# esp32_display_schema.net
KiCad netlist of a schematic drawn in EasyEDA
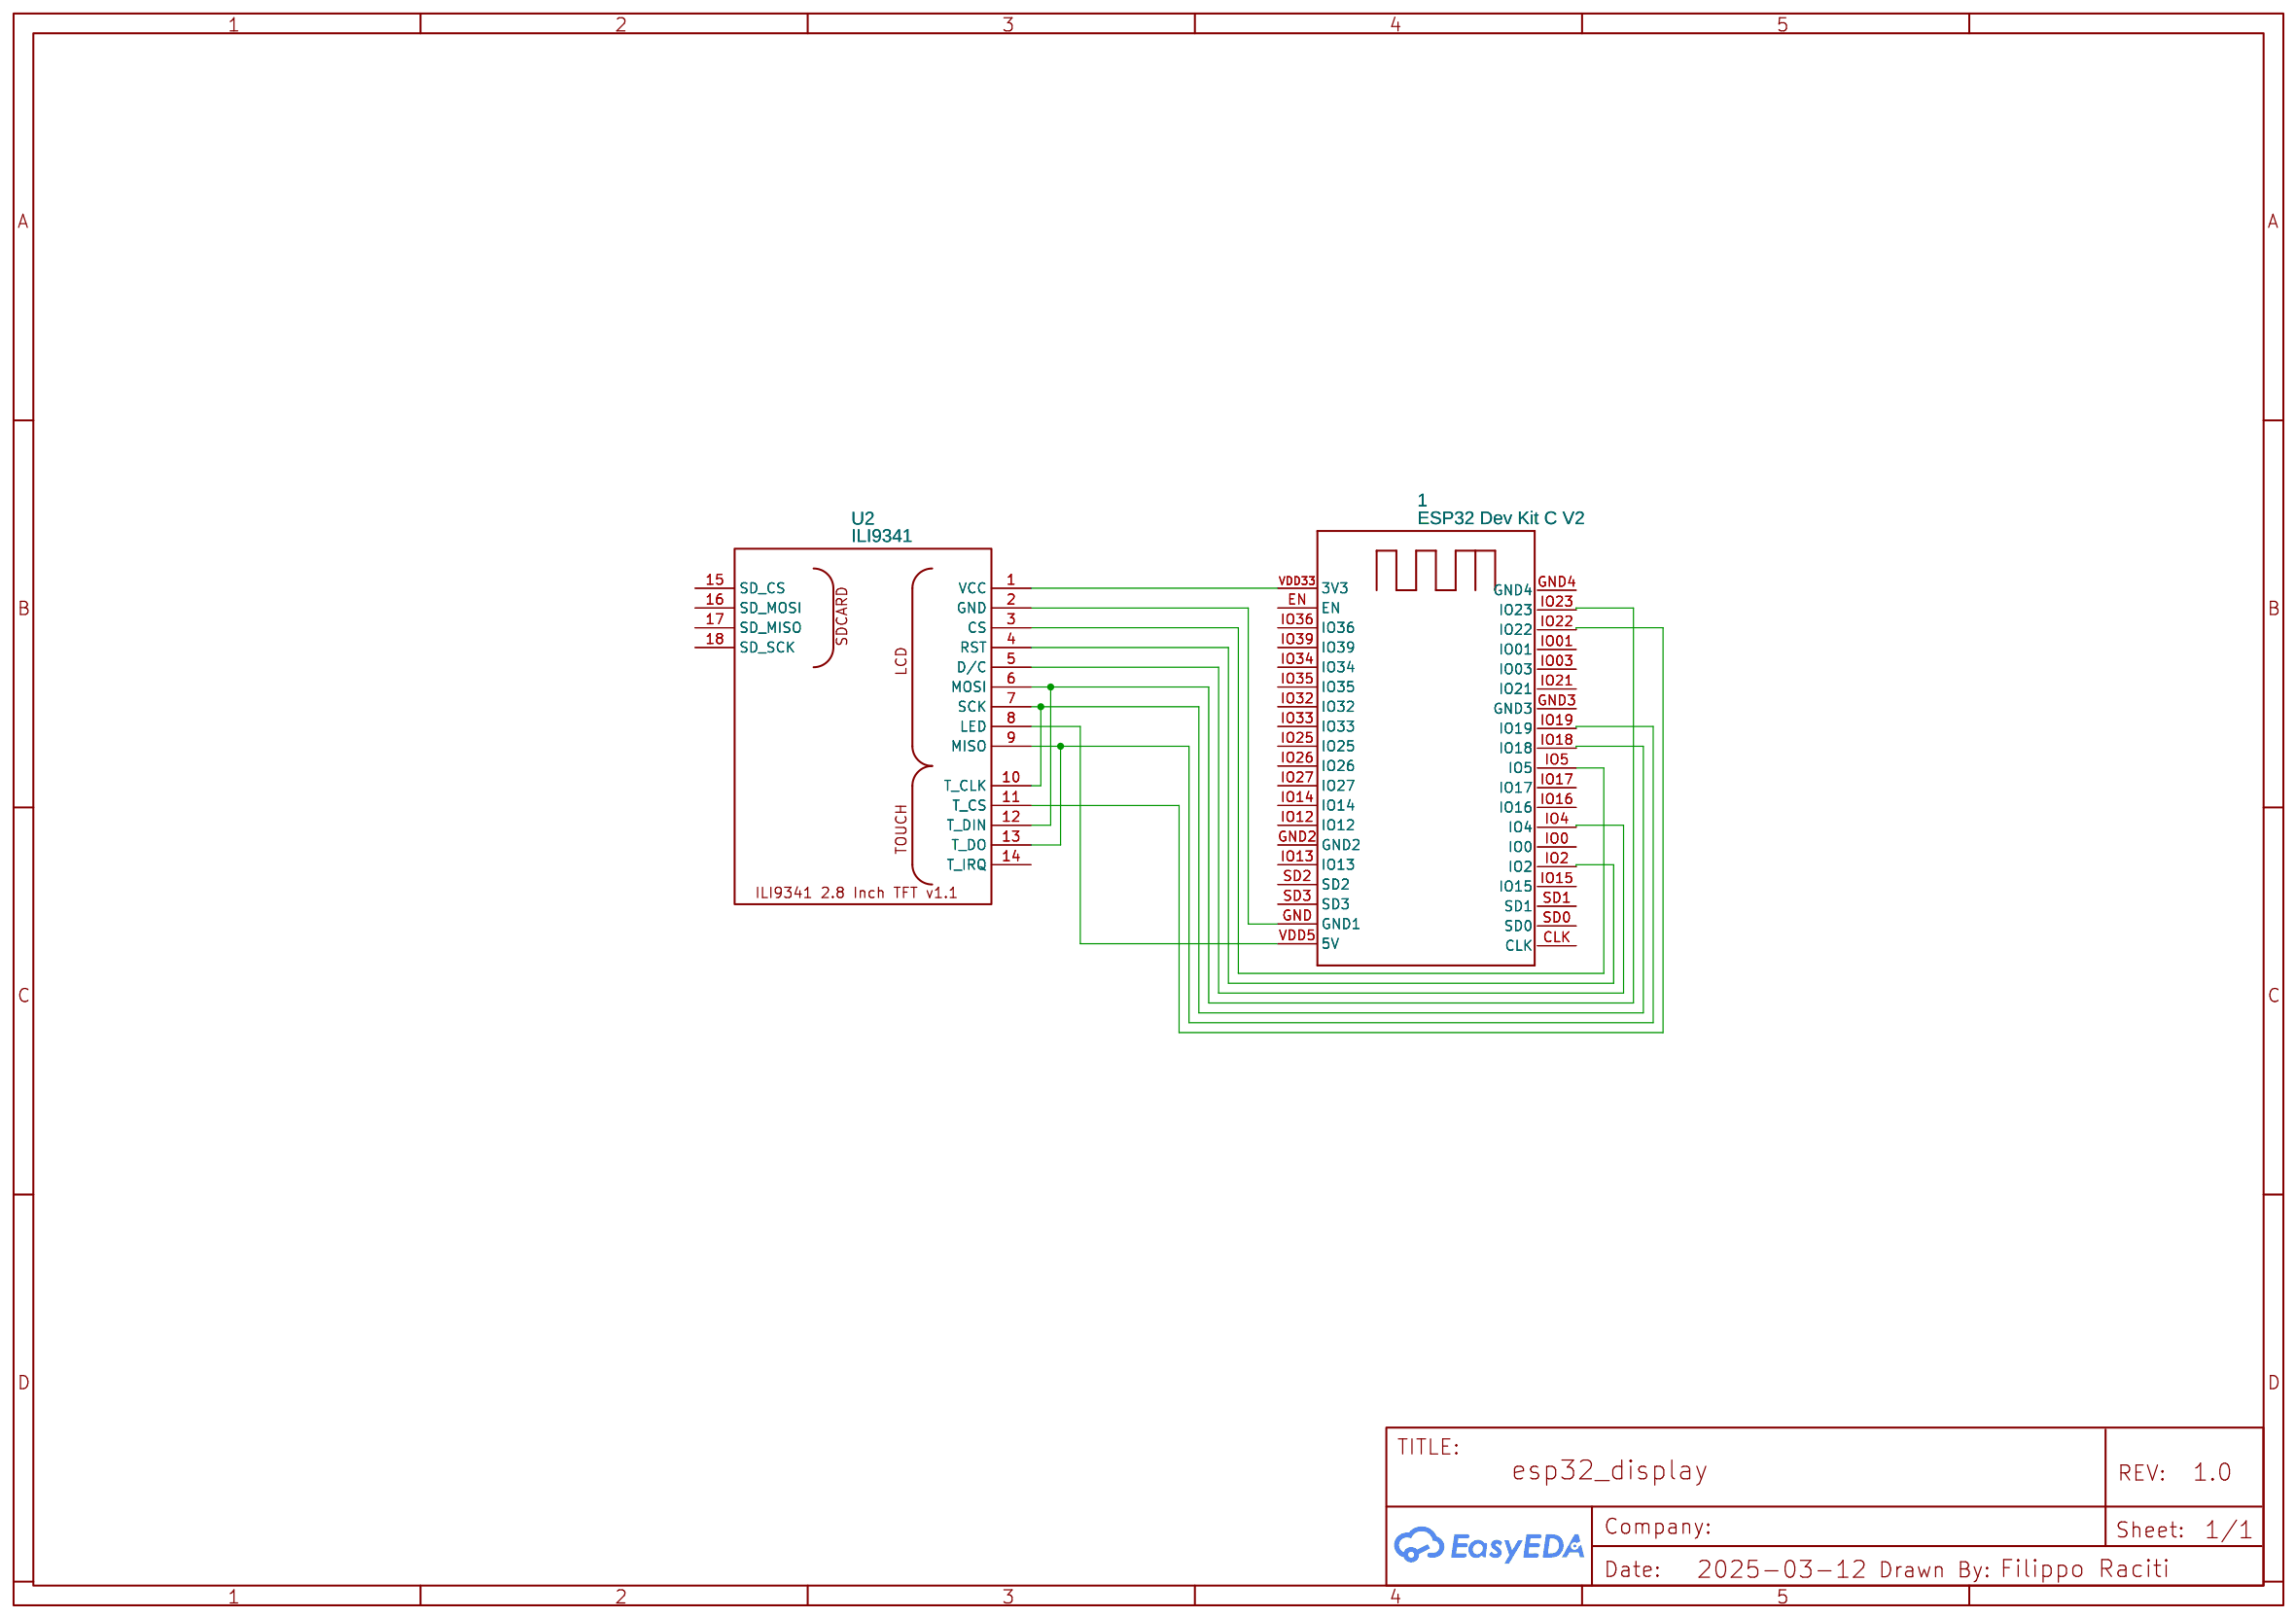
[diagram p0: schematic sheet]

(export (version "E")
  (design (tool "Eeschema 10.0.6"))
  (components
    (comp (ref "1") (value "ESP32 Dev Kit C V2") (libsource (lib "") (part "ESP32 Dev Kit C V2")))
    (comp (ref "U2") (value "ILI9341") (libsource (lib "") (part "ILI9341")))
  )
  (nets
    (net (code "1") (name "Net-(1-3V3)") (class "Default")
      (node (ref "1") (pin "VDD33") (pinfunction "3V3_VDD33") (pintype "unspecified"))
      (node (ref "U2") (pin "1") (pinfunction "VCC_1") (pintype "unspecified"))
    )
    (net (code "2") (name "Net-(1-5V)") (class "Default")
      (node (ref "1") (pin "VDD5") (pinfunction "5V_VDD5") (pintype "unspecified"))
      (node (ref "U2") (pin "8") (pinfunction "LED_8") (pintype "unspecified"))
    )
    (net (code "3") (name "Net-(1-GND1)") (class "Default")
      (node (ref "1") (pin "GND") (pinfunction "GND1_GND") (pintype "unspecified"))
      (node (ref "U2") (pin "2") (pinfunction "GND_2") (pintype "unspecified"))
    )
    (net (code "4") (name "Net-(U2-CS)") (class "Default")
      (node (ref "1") (pin "IO5") (pinfunction "IO5_IO5") (pintype "unspecified"))
      (node (ref "U2") (pin "3") (pinfunction "CS_3") (pintype "unspecified"))
    )
    (net (code "5") (name "Net-(U2-D{slash}C)") (class "Default")
      (node (ref "1") (pin "IO4") (pinfunction "IO4_IO4") (pintype "unspecified"))
      (node (ref "U2") (pin "5") (pinfunction "D/C_5") (pintype "unspecified"))
    )
    (net (code "6") (name "Net-(U2-MISO)") (class "Default")
      (node (ref "1") (pin "IO19") (pinfunction "IO19_IO19") (pintype "unspecified"))
      (node (ref "U2") (pin "13") (pinfunction "T_DO_13") (pintype "unspecified"))
      (node (ref "U2") (pin "9") (pinfunction "MISO_9") (pintype "unspecified"))
    )
    (net (code "7") (name "Net-(U2-MOSI)") (class "Default")
      (node (ref "1") (pin "IO23") (pinfunction "IO23_IO23") (pintype "unspecified"))
      (node (ref "U2") (pin "12") (pinfunction "T_DIN_12") (pintype "unspecified"))
      (node (ref "U2") (pin "6") (pinfunction "MOSI_6") (pintype "unspecified"))
    )
    (net (code "8") (name "Net-(U2-RST)") (class "Default")
      (node (ref "1") (pin "IO2") (pinfunction "IO2_IO2") (pintype "unspecified"))
      (node (ref "U2") (pin "4") (pinfunction "RST_4") (pintype "unspecified"))
    )
    (net (code "9") (name "Net-(U2-SCK)") (class "Default")
      (node (ref "1") (pin "IO18") (pinfunction "IO18_IO18") (pintype "unspecified"))
      (node (ref "U2") (pin "10") (pinfunction "T_CLK_10") (pintype "unspecified"))
      (node (ref "U2") (pin "7") (pinfunction "SCK_7") (pintype "unspecified"))
    )
    (net (code "10") (name "Net-(U2-T_CS)") (class "Default")
      (node (ref "1") (pin "IO22") (pinfunction "IO22_IO22") (pintype "unspecified"))
      (node (ref "U2") (pin "11") (pinfunction "T_CS_11") (pintype "unspecified"))
    )
    (net (code "11") (name "unconnected-(1-PadCLK)") (class "Default")
      (node (ref "1") (pin "CLK") (pinfunction "CLK_CLK") (pintype "unspecified"))
    )
    (net (code "12") (name "unconnected-(1-PadEN)") (class "Default")
      (node (ref "1") (pin "EN") (pinfunction "EN_EN") (pintype "unspecified"))
    )
    (net (code "13") (name "unconnected-(1-PadGND2)") (class "Default")
      (node (ref "1") (pin "GND2") (pinfunction "GND2_GND2") (pintype "unspecified"))
    )
    (net (code "14") (name "unconnected-(1-PadGND3)") (class "Default")
      (node (ref "1") (pin "GND3") (pinfunction "GND3_GND3") (pintype "unspecified"))
    )
    (net (code "15") (name "unconnected-(1-PadGND4)") (class "Default")
      (node (ref "1") (pin "GND4") (pinfunction "GND4_GND4") (pintype "unspecified"))
    )
    (net (code "16") (name "unconnected-(1-PadIO0)") (class "Default")
      (node (ref "1") (pin "IO0") (pinfunction "IO0_IO0") (pintype "unspecified"))
    )
    (net (code "17") (name "unconnected-(1-PadIO01)") (class "Default")
      (node (ref "1") (pin "IO01") (pinfunction "IO01_IO01") (pintype "unspecified"))
    )
    (net (code "18") (name "unconnected-(1-PadIO03)") (class "Default")
      (node (ref "1") (pin "IO03") (pinfunction "IO03_IO03") (pintype "unspecified"))
    )
    (net (code "19") (name "unconnected-(1-PadIO12)") (class "Default")
      (node (ref "1") (pin "IO12") (pinfunction "IO12_IO12") (pintype "unspecified"))
    )
    (net (code "20") (name "unconnected-(1-PadIO13)") (class "Default")
      (node (ref "1") (pin "IO13") (pinfunction "IO13_IO13") (pintype "unspecified"))
    )
    (net (code "21") (name "unconnected-(1-PadIO14)") (class "Default")
      (node (ref "1") (pin "IO14") (pinfunction "IO14_IO14") (pintype "unspecified"))
    )
    (net (code "22") (name "unconnected-(1-PadIO15)") (class "Default")
      (node (ref "1") (pin "IO15") (pinfunction "IO15_IO15") (pintype "unspecified"))
    )
    (net (code "23") (name "unconnected-(1-PadIO16)") (class "Default")
      (node (ref "1") (pin "IO16") (pinfunction "IO16_IO16") (pintype "unspecified"))
    )
    (net (code "24") (name "unconnected-(1-PadIO17)") (class "Default")
      (node (ref "1") (pin "IO17") (pinfunction "IO17_IO17") (pintype "unspecified"))
    )
    (net (code "25") (name "unconnected-(1-PadIO21)") (class "Default")
      (node (ref "1") (pin "IO21") (pinfunction "IO21_IO21") (pintype "unspecified"))
    )
    (net (code "26") (name "unconnected-(1-PadIO25)") (class "Default")
      (node (ref "1") (pin "IO25") (pinfunction "IO25_IO25") (pintype "unspecified"))
    )
    (net (code "27") (name "unconnected-(1-PadIO26)") (class "Default")
      (node (ref "1") (pin "IO26") (pinfunction "IO26_IO26") (pintype "unspecified"))
    )
    (net (code "28") (name "unconnected-(1-PadIO27)") (class "Default")
      (node (ref "1") (pin "IO27") (pinfunction "IO27_IO27") (pintype "unspecified"))
    )
    (net (code "29") (name "unconnected-(1-PadIO32)") (class "Default")
      (node (ref "1") (pin "IO32") (pinfunction "IO32_IO32") (pintype "unspecified"))
    )
    (net (code "30") (name "unconnected-(1-PadIO33)") (class "Default")
      (node (ref "1") (pin "IO33") (pinfunction "IO33_IO33") (pintype "unspecified"))
    )
    (net (code "31") (name "unconnected-(1-PadIO34)") (class "Default")
      (node (ref "1") (pin "IO34") (pinfunction "IO34_IO34") (pintype "unspecified"))
    )
    (net (code "32") (name "unconnected-(1-PadIO35)") (class "Default")
      (node (ref "1") (pin "IO35") (pinfunction "IO35_IO35") (pintype "unspecified"))
    )
    (net (code "33") (name "unconnected-(1-PadIO36)") (class "Default")
      (node (ref "1") (pin "IO36") (pinfunction "IO36_IO36") (pintype "unspecified"))
    )
    (net (code "34") (name "unconnected-(1-PadIO39)") (class "Default")
      (node (ref "1") (pin "IO39") (pinfunction "IO39_IO39") (pintype "unspecified"))
    )
    (net (code "35") (name "unconnected-(1-PadSD0)") (class "Default")
      (node (ref "1") (pin "SD0") (pinfunction "SD0_SD0") (pintype "unspecified"))
    )
    (net (code "36") (name "unconnected-(1-PadSD1)") (class "Default")
      (node (ref "1") (pin "SD1") (pinfunction "SD1_SD1") (pintype "unspecified"))
    )
    (net (code "37") (name "unconnected-(1-PadSD2)") (class "Default")
      (node (ref "1") (pin "SD2") (pinfunction "SD2_SD2") (pintype "unspecified"))
    )
    (net (code "38") (name "unconnected-(1-PadSD3)") (class "Default")
      (node (ref "1") (pin "SD3") (pinfunction "SD3_SD3") (pintype "unspecified"))
    )
    (net (code "39") (name "unconnected-(U2-SD_CS-Pad15)") (class "Default")
      (node (ref "U2") (pin "15") (pinfunction "SD_CS_15") (pintype "unspecified"))
    )
    (net (code "40") (name "unconnected-(U2-SD_MISO-Pad17)") (class "Default")
      (node (ref "U2") (pin "17") (pinfunction "SD_MISO_17") (pintype "unspecified"))
    )
    (net (code "41") (name "unconnected-(U2-SD_MOSI-Pad16)") (class "Default")
      (node (ref "U2") (pin "16") (pinfunction "SD_MOSI_16") (pintype "unspecified"))
    )
    (net (code "42") (name "unconnected-(U2-SD_SCK-Pad18)") (class "Default")
      (node (ref "U2") (pin "18") (pinfunction "SD_SCK_18") (pintype "unspecified"))
    )
    (net (code "43") (name "unconnected-(U2-T_IRQ-Pad14)") (class "Default")
      (node (ref "U2") (pin "14") (pinfunction "T_IRQ_14") (pintype "unspecified"))
    )
  )
)
